# xbee-radio.net
KiCad netlist of a schematic drawn in EAGLE
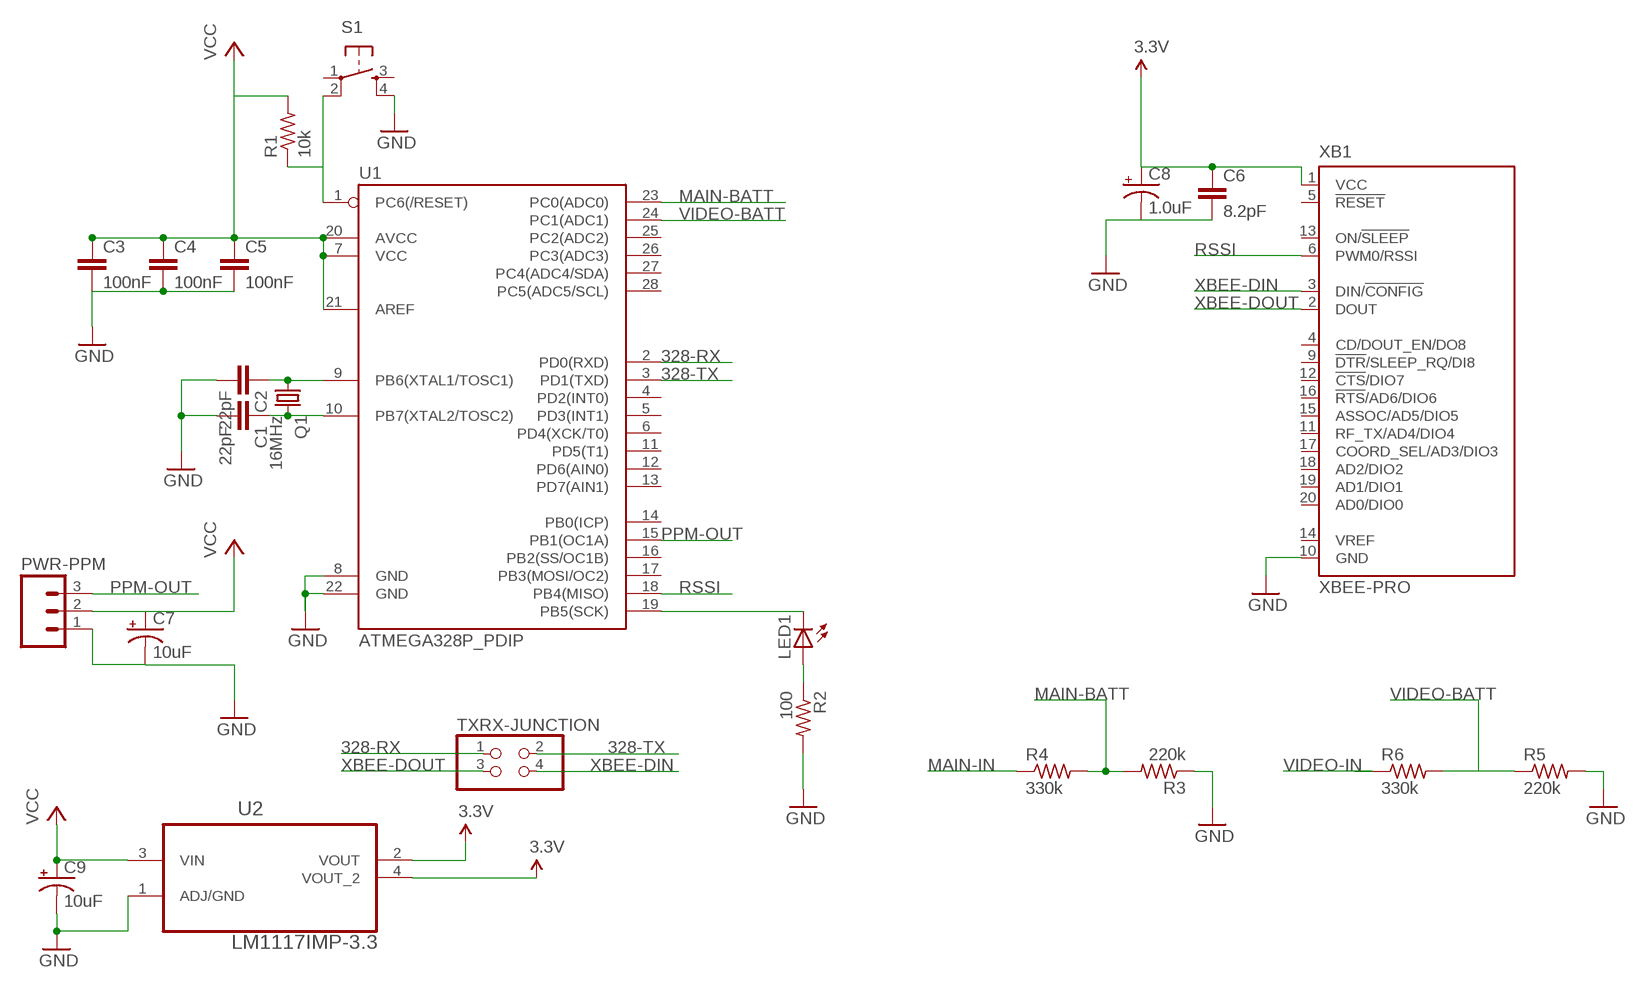
[diagram p0: schematic, sheet 1]

(export (version "E")
  (design (tool "Eeschema 10.0.6"))
  (components
    (comp (ref "C1")
      (value "22pF")
      (footprint "eagle-import:C2.5-2")
      (libsource (lib "eagle-import") (part "C2.5/2"))
    )
    (comp (ref "C2")
      (value "22pF")
      (footprint "eagle-import:C2.5-2")
      (libsource (lib "eagle-import") (part "C2.5/2"))
    )
    (comp (ref "C3")
      (value "100nF")
      (footprint "eagle-import:C2.5-2")
      (libsource (lib "eagle-import") (part "C2.5/2"))
    )
    (comp (ref "C4")
      (value "100nF")
      (footprint "eagle-import:C2.5-2")
      (libsource (lib "eagle-import") (part "C2.5/2"))
    )
    (comp (ref "C5")
      (value "100nF")
      (footprint "eagle-import:C2.5-2")
      (libsource (lib "eagle-import") (part "C2.5/2"))
    )
    (comp (ref "C6")
      (value "8.2pF")
      (footprint "eagle-import:C2.5-2")
      (libsource (lib "eagle-import") (part "C2.5/2"))
    )
    (comp (ref "C7")
      (value "10uF")
      (footprint "eagle-import:E2-5")
      (libsource (lib "eagle-import") (part "CPOL-USE2-5"))
    )
    (comp (ref "C8")
      (value "1.0uF")
      (footprint "eagle-import:E2-5")
      (libsource (lib "eagle-import") (part "CPOL-USE2-5"))
    )
    (comp (ref "C9")
      (value "10uF")
      (footprint "eagle-import:E2-5")
      (libsource (lib "eagle-import") (part "CPOL-USE2-5"))
    )
    (comp (ref "LED1")
      (value "LED3MM")
      (footprint "eagle-import:LED3MM")
      (libsource (lib "eagle-import") (part "LED3MM"))
    )
    (comp (ref "PWR-PPM")
      (value "M03PTH")
      (footprint "eagle-import:1X03")
      (libsource (lib "eagle-import") (part "M03PTH"))
    )
    (comp (ref "Q1")
      (value "16MHz")
      (footprint "eagle-import:TC26V")
      (libsource (lib "eagle-import") (part "CRYSTALTC26V"))
    )
    (comp (ref "R1")
      (value "10k")
      (footprint "eagle-import:0204_5")
      (libsource (lib "eagle-import") (part "R-US_0204/5"))
    )
    (comp (ref "R2")
      (value "100")
      (footprint "eagle-import:0204_5")
      (libsource (lib "eagle-import") (part "R-US_0204/5"))
    )
    (comp (ref "R3")
      (value "220k")
      (footprint "eagle-import:0204_5")
      (libsource (lib "eagle-import") (part "R-US_0204/5"))
    )
    (comp (ref "R4")
      (value "330k")
      (footprint "eagle-import:0204_5")
      (libsource (lib "eagle-import") (part "R-US_0204/5"))
    )
    (comp (ref "R5")
      (value "220k")
      (footprint "eagle-import:0204_5")
      (libsource (lib "eagle-import") (part "R-US_0204/5"))
    )
    (comp (ref "R6")
      (value "330k")
      (footprint "eagle-import:0204_5")
      (libsource (lib "eagle-import") (part "R-US_0204/5"))
    )
    (comp (ref "S1")
      (value "TAC_SWITCHPTH")
      (footprint "eagle-import:TACTILE-PTH")
      (libsource (lib "eagle-import") (part "TAC_SWITCHPTH"))
    )
    (comp (ref "TXRX-JUNCTION")
      (value "PINHD-2X2")
      (footprint "eagle-import:2X02")
      (libsource (lib "eagle-import") (part "PINHD-2X2"))
    )
    (comp (ref "U1")
      (value "ATMEGA328P_PDIP")
      (footprint "eagle-import:DIL28-3")
      (libsource (lib "eagle-import") (part "ATMEGA328P_PDIP"))
    )
    (comp (ref "U2")
      (value "LM1117IMP-3.3")
      (footprint "eagle-import:SOT230P696X180-4N")
      (libsource (lib "eagle-import") (part "LM1117IMP-3.3"))
    )
    (comp (ref "XB1")
      (value "XBEE-PRO")
      (footprint "eagle-import:XBEE-PRO")
      (fields (field (name "MPN") "XBP24-AWI-001"))
      (libsource (lib "eagle-import") (part "XBEE-PRO"))
    )
  )
  (nets
    (net (code "1") (name "/328-RX") (class "Default")
      (node (ref "TXRX-JUNCTION") (pin "1") (pinfunction "1_1") (pintype "passive"))
      (node (ref "U1") (pin "2") (pinfunction "PD0(RXD)_2") (pintype "bidirectional"))
    )
    (net (code "2") (name "/328-TX") (class "Default")
      (node (ref "TXRX-JUNCTION") (pin "2") (pinfunction "2_2") (pintype "passive"))
      (node (ref "U1") (pin "3") (pinfunction "PD1(TXD)_3") (pintype "bidirectional"))
    )
    (net (code "3") (name "/MAIN-BATT") (class "Default")
      (node (ref "R3") (pin "2") (pinfunction "2_2") (pintype "passive"))
      (node (ref "R4") (pin "2") (pinfunction "2_2") (pintype "passive"))
      (node (ref "U1") (pin "23") (pinfunction "PC0(ADC0)_23") (pintype "bidirectional"))
    )
    (net (code "4") (name "/MAIN-IN") (class "Default")
      (node (ref "R4") (pin "1") (pinfunction "1_1") (pintype "passive"))
    )
    (net (code "5") (name "/PPM-OUT") (class "Default")
      (node (ref "PWR-PPM") (pin "3") (pinfunction "3_3") (pintype "passive"))
      (node (ref "U1") (pin "15") (pinfunction "PB1(OC1A)_15") (pintype "bidirectional"))
    )
    (net (code "6") (name "/RSSI") (class "Default")
      (node (ref "U1") (pin "18") (pinfunction "PB4(MISO)_18") (pintype "bidirectional"))
      (node (ref "XB1") (pin "6") (pinfunction "PWM0/RSSI_6") (pintype "output"))
    )
    (net (code "7") (name "/VIDEO-BATT") (class "Default")
      (node (ref "R5") (pin "1") (pinfunction "1_1") (pintype "passive"))
      (node (ref "R6") (pin "2") (pinfunction "2_2") (pintype "passive"))
      (node (ref "U1") (pin "24") (pinfunction "PC1(ADC1)_24") (pintype "bidirectional"))
    )
    (net (code "8") (name "/VIDEO-IN") (class "Default")
      (node (ref "R6") (pin "1") (pinfunction "1_1") (pintype "passive"))
    )
    (net (code "9") (name "/XBEE-DIN") (class "Default")
      (node (ref "TXRX-JUNCTION") (pin "4") (pinfunction "4_4") (pintype "passive"))
      (node (ref "XB1") (pin "3") (pinfunction "DIN/~{CONFIG}_3") (pintype "input"))
    )
    (net (code "10") (name "/XBEE-DOUT") (class "Default")
      (node (ref "TXRX-JUNCTION") (pin "3") (pinfunction "3_3") (pintype "passive"))
      (node (ref "XB1") (pin "2") (pinfunction "DOUT_2") (pintype "output"))
    )
    (net (code "11") (name "3.3V") (class "Default")
      (node (ref "C6") (pin "1") (pinfunction "1_1") (pintype "passive"))
      (node (ref "C8") (pin "+") (pinfunction "+_+") (pintype "passive"))
      (node (ref "U2") (pin "2") (pinfunction "VOUT_2") (pintype "output"))
      (node (ref "U2") (pin "4") (pinfunction "VOUT_2_4") (pintype "output"))
      (node (ref "XB1") (pin "1") (pinfunction "VCC_1") (pintype "power_in"))
    )
    (net (code "12") (name "GND") (class "Default")
      (node (ref "C1") (pin "2") (pinfunction "2_2") (pintype "passive"))
      (node (ref "C2") (pin "2") (pinfunction "2_2") (pintype "passive"))
      (node (ref "C3") (pin "2") (pinfunction "2_2") (pintype "passive"))
      (node (ref "C4") (pin "2") (pinfunction "2_2") (pintype "passive"))
      (node (ref "C5") (pin "2") (pinfunction "2_2") (pintype "passive"))
      (node (ref "C6") (pin "2") (pinfunction "2_2") (pintype "passive"))
      (node (ref "C7") (pin "-") (pinfunction "-_-") (pintype "passive"))
      (node (ref "C8") (pin "-") (pinfunction "-_-") (pintype "passive"))
      (node (ref "C9") (pin "-") (pinfunction "-_-") (pintype "passive"))
      (node (ref "PWR-PPM") (pin "1") (pinfunction "1_1") (pintype "passive"))
      (node (ref "R2") (pin "2") (pinfunction "2_2") (pintype "passive"))
      (node (ref "R3") (pin "1") (pinfunction "1_1") (pintype "passive"))
      (node (ref "R5") (pin "2") (pinfunction "2_2") (pintype "passive"))
      (node (ref "S1") (pin "4") (pinfunction "4_4") (pintype "passive"))
      (node (ref "U1") (pin "22") (pinfunction "GND_22") (pintype "bidirectional"))
      (node (ref "U1") (pin "8") (pinfunction "GND_8") (pintype "bidirectional"))
      (node (ref "U2") (pin "1") (pinfunction "ADJ/GND_1") (pintype "passive"))
      (node (ref "XB1") (pin "10") (pinfunction "GND_10") (pintype "power_in"))
    )
    (net (code "13") (name "Net-(LED1-C)") (class "Default")
      (node (ref "LED1") (pin "K") (pinfunction "C_K") (pintype "passive"))
      (node (ref "U1") (pin "19") (pinfunction "PB5(SCK)_19") (pintype "bidirectional"))
    )
    (net (code "14") (name "Net-(LED1-PadA)") (class "Default")
      (node (ref "LED1") (pin "A") (pinfunction "A_A") (pintype "passive"))
      (node (ref "R2") (pin "1") (pinfunction "1_1") (pintype "passive"))
    )
    (net (code "15") (name "Net-(U1-PB6(XTAL1{slash}TOSC1))") (class "Default")
      (node (ref "C2") (pin "1") (pinfunction "1_1") (pintype "passive"))
      (node (ref "Q1") (pin "1") (pinfunction "1_1") (pintype "passive"))
      (node (ref "U1") (pin "9") (pinfunction "PB6(XTAL1/TOSC1)_9") (pintype "bidirectional"))
    )
    (net (code "16") (name "Net-(U1-PB7(XTAL2{slash}TOSC2))") (class "Default")
      (node (ref "C1") (pin "1") (pinfunction "1_1") (pintype "passive"))
      (node (ref "Q1") (pin "2") (pinfunction "2_2") (pintype "passive"))
      (node (ref "U1") (pin "10") (pinfunction "PB7(XTAL2/TOSC2)_10") (pintype "bidirectional"))
    )
    (net (code "17") (name "Net-(U1-PC6({slash}RESET))") (class "Default")
      (node (ref "R1") (pin "1") (pinfunction "1_1") (pintype "passive"))
      (node (ref "S1") (pin "2") (pinfunction "2_2") (pintype "passive"))
      (node (ref "U1") (pin "1") (pinfunction "PC6(/RESET)_1") (pintype "bidirectional"))
    )
    (net (code "18") (name "VCC") (class "Default")
      (node (ref "C3") (pin "1") (pinfunction "1_1") (pintype "passive"))
      (node (ref "C4") (pin "1") (pinfunction "1_1") (pintype "passive"))
      (node (ref "C5") (pin "1") (pinfunction "1_1") (pintype "passive"))
      (node (ref "C7") (pin "+") (pinfunction "+_+") (pintype "passive"))
      (node (ref "C9") (pin "+") (pinfunction "+_+") (pintype "passive"))
      (node (ref "PWR-PPM") (pin "2") (pinfunction "2_2") (pintype "passive"))
      (node (ref "R1") (pin "2") (pinfunction "2_2") (pintype "passive"))
      (node (ref "U1") (pin "20") (pinfunction "AVCC_20") (pintype "bidirectional"))
      (node (ref "U1") (pin "21") (pinfunction "AREF_21") (pintype "bidirectional"))
      (node (ref "U1") (pin "7") (pinfunction "VCC_7") (pintype "bidirectional"))
      (node (ref "U2") (pin "3") (pinfunction "VIN_3") (pintype "input"))
    )
    (net (code "19") (name "unconnected-(S1-Pad1)") (class "Default")
      (node (ref "S1") (pin "1") (pinfunction "1_1") (pintype "passive"))
    )
    (net (code "20") (name "unconnected-(S1-Pad3)") (class "Default")
      (node (ref "S1") (pin "3") (pinfunction "3_3") (pintype "passive"))
    )
    (net (code "21") (name "unconnected-(U1-PB0(ICP)-Pad14)") (class "Default")
      (node (ref "U1") (pin "14") (pinfunction "PB0(ICP)_14") (pintype "bidirectional"))
    )
    (net (code "22") (name "unconnected-(U1-PB2(SS{slash}OC1B)-Pad16)") (class "Default")
      (node (ref "U1") (pin "16") (pinfunction "PB2(SS/OC1B)_16") (pintype "bidirectional"))
    )
    (net (code "23") (name "unconnected-(U1-PB3(MOSI{slash}OC2)-Pad17)") (class "Default")
      (node (ref "U1") (pin "17") (pinfunction "PB3(MOSI/OC2)_17") (pintype "bidirectional"))
    )
    (net (code "24") (name "unconnected-(U1-PC2(ADC2)-Pad25)") (class "Default")
      (node (ref "U1") (pin "25") (pinfunction "PC2(ADC2)_25") (pintype "bidirectional"))
    )
    (net (code "25") (name "unconnected-(U1-PC3(ADC3)-Pad26)") (class "Default")
      (node (ref "U1") (pin "26") (pinfunction "PC3(ADC3)_26") (pintype "bidirectional"))
    )
    (net (code "26") (name "unconnected-(U1-PC4(ADC4{slash}SDA)-Pad27)") (class "Default")
      (node (ref "U1") (pin "27") (pinfunction "PC4(ADC4/SDA)_27") (pintype "bidirectional"))
    )
    (net (code "27") (name "unconnected-(U1-PC5(ADC5{slash}SCL)-Pad28)") (class "Default")
      (node (ref "U1") (pin "28") (pinfunction "PC5(ADC5/SCL)_28") (pintype "bidirectional"))
    )
    (net (code "28") (name "unconnected-(U1-PD2(INT0)-Pad4)") (class "Default")
      (node (ref "U1") (pin "4") (pinfunction "PD2(INT0)_4") (pintype "bidirectional"))
    )
    (net (code "29") (name "unconnected-(U1-PD3(INT1)-Pad5)") (class "Default")
      (node (ref "U1") (pin "5") (pinfunction "PD3(INT1)_5") (pintype "bidirectional"))
    )
    (net (code "30") (name "unconnected-(U1-PD4(XCK{slash}T0)-Pad6)") (class "Default")
      (node (ref "U1") (pin "6") (pinfunction "PD4(XCK/T0)_6") (pintype "bidirectional"))
    )
    (net (code "31") (name "unconnected-(U1-PD5(T1)-Pad11)") (class "Default")
      (node (ref "U1") (pin "11") (pinfunction "PD5(T1)_11") (pintype "bidirectional"))
    )
    (net (code "32") (name "unconnected-(U1-PD6(AIN0)-Pad12)") (class "Default")
      (node (ref "U1") (pin "12") (pinfunction "PD6(AIN0)_12") (pintype "bidirectional"))
    )
    (net (code "33") (name "unconnected-(U1-PD7(AIN1)-Pad13)") (class "Default")
      (node (ref "U1") (pin "13") (pinfunction "PD7(AIN1)_13") (pintype "bidirectional"))
    )
    (net (code "34") (name "unconnected-(XB1-AD0{slash}DIO0-Pad20)") (class "Default")
      (node (ref "XB1") (pin "20") (pinfunction "AD0/DIO0_20") (pintype "bidirectional"))
    )
    (net (code "35") (name "unconnected-(XB1-AD1{slash}DIO1-Pad19)") (class "Default")
      (node (ref "XB1") (pin "19") (pinfunction "AD1/DIO1_19") (pintype "bidirectional"))
    )
    (net (code "36") (name "unconnected-(XB1-AD2{slash}DIO2-Pad18)") (class "Default")
      (node (ref "XB1") (pin "18") (pinfunction "AD2/DIO2_18") (pintype "bidirectional"))
    )
    (net (code "37") (name "unconnected-(XB1-ASSOC{slash}AD5{slash}DIO5-Pad15)") (class "Default")
      (node (ref "XB1") (pin "15") (pinfunction "ASSOC/AD5/DIO5_15") (pintype "bidirectional"))
    )
    (net (code "38") (name "unconnected-(XB1-CD{slash}DOUT_EN{slash}DO8-Pad4)") (class "Default")
      (node (ref "XB1") (pin "4") (pinfunction "CD/DOUT_EN/DO8_4") (pintype "output"))
    )
    (net (code "39") (name "unconnected-(XB1-COORD_SEL{slash}AD3{slash}DIO3-Pad17)") (class "Default")
      (node (ref "XB1") (pin "17") (pinfunction "COORD_SEL/AD3/DIO3_17") (pintype "bidirectional"))
    )
    (net (code "40") (name "unconnected-(XB1-ON{slash}~{SLEEP}-Pad13)") (class "Default")
      (node (ref "XB1") (pin "13") (pinfunction "ON/~{SLEEP}_13") (pintype "output"))
    )
    (net (code "41") (name "unconnected-(XB1-RF_TX{slash}AD4{slash}DIO4-Pad11)") (class "Default")
      (node (ref "XB1") (pin "11") (pinfunction "RF_TX/AD4/DIO4_11") (pintype "bidirectional"))
    )
    (net (code "42") (name "unconnected-(XB1-VREF-Pad14)") (class "Default")
      (node (ref "XB1") (pin "14") (pinfunction "VREF_14") (pintype "input"))
    )
    (net (code "43") (name "unconnected-(XB1-~{CTS}{slash}DIO7-Pad12)") (class "Default")
      (node (ref "XB1") (pin "12") (pinfunction "~{CTS}/DIO7_12") (pintype "bidirectional"))
    )
    (net (code "44") (name "unconnected-(XB1-~{DTR}{slash}SLEEP_RQ{slash}DI8-Pad9)") (class "Default")
      (node (ref "XB1") (pin "9") (pinfunction "~{DTR}/SLEEP_RQ/DI8_9") (pintype "bidirectional"))
    )
    (net (code "45") (name "unconnected-(XB1-~{RESET}-Pad5)") (class "Default")
      (node (ref "XB1") (pin "5") (pinfunction "~{RESET}_5") (pintype "input"))
    )
    (net (code "46") (name "unconnected-(XB1-~{RTS}{slash}AD6{slash}DIO6-Pad16)") (class "Default")
      (node (ref "XB1") (pin "16") (pinfunction "~{RTS}/AD6/DIO6_16") (pintype "bidirectional"))
    )
  )
)
